# motor_endcap.net
KiCad netlist of a schematic drawn in Altium Designer
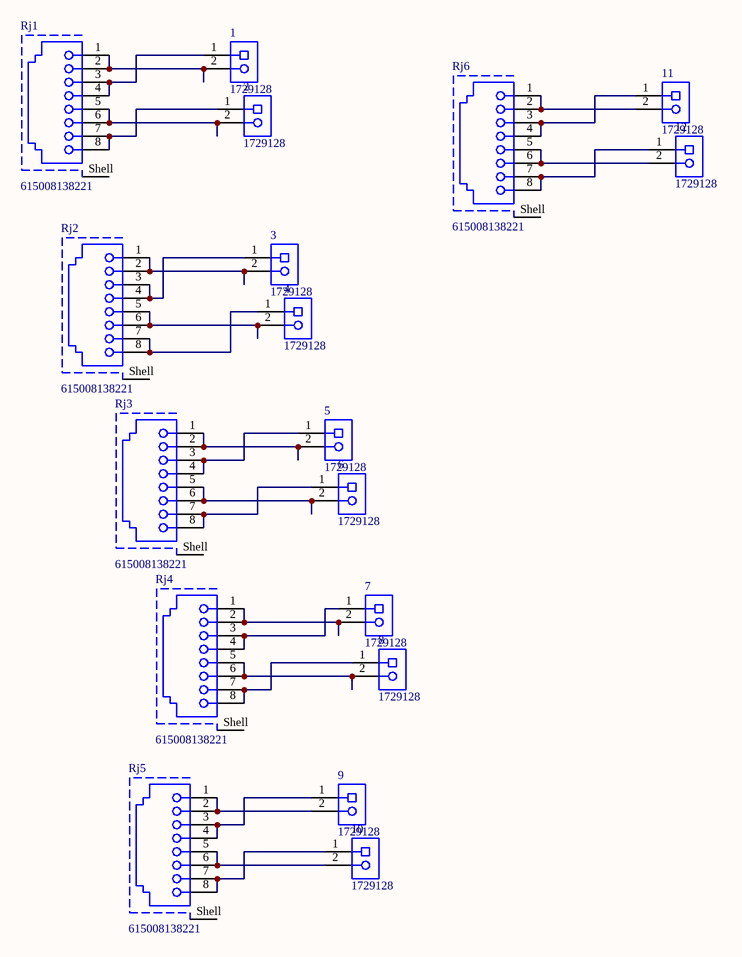
[diagram p0: motor endcap.SchDoc]

(export (version "E")
  (design (tool "Eeschema 10.0.6"))
  (components
    (comp (ref "1")
      (value "1729128")
      (footprint "PHOE-1729128-2_V")
      (description "PCB Terminal Block, 13.5 A, 400 V, 2-Pin THD, RoHS, Bulk")
      (fields (field (name "MANUFACTURER") "Phoenix Contact"))
      (libsource (lib "Altium Content Vault") (part "CN-2P-F-R2"))
    )
    (comp (ref "2")
      (value "1729128")
      (footprint "PHOE-1729128-2_V")
      (description "PCB Terminal Block, 13.5 A, 400 V, 2-Pin THD, RoHS, Bulk")
      (fields (field (name "MANUFACTURER") "Phoenix Contact"))
      (libsource (lib "Altium Content Vault") (part "CN-2P-F-R2"))
    )
    (comp (ref "3")
      (value "1729128")
      (footprint "PHOE-1729128-2_V")
      (description "PCB Terminal Block, 13.5 A, 400 V, 2-Pin THD, RoHS, Bulk")
      (fields (field (name "MANUFACTURER") "Phoenix Contact"))
      (libsource (lib "Altium Content Vault") (part "CN-2P-F-R2"))
    )
    (comp (ref "4")
      (value "1729128")
      (footprint "PHOE-1729128-2_V")
      (description "PCB Terminal Block, 13.5 A, 400 V, 2-Pin THD, RoHS, Bulk")
      (fields (field (name "MANUFACTURER") "Phoenix Contact"))
      (libsource (lib "Altium Content Vault") (part "CN-2P-F-R2"))
    )
    (comp (ref "5")
      (value "1729128")
      (footprint "PHOE-1729128-2_V")
      (description "PCB Terminal Block, 13.5 A, 400 V, 2-Pin THD, RoHS, Bulk")
      (fields (field (name "MANUFACTURER") "Phoenix Contact"))
      (libsource (lib "Altium Content Vault") (part "CN-2P-F-R2"))
    )
    (comp (ref "6")
      (value "1729128")
      (footprint "PHOE-1729128-2_V")
      (description "PCB Terminal Block, 13.5 A, 400 V, 2-Pin THD, RoHS, Bulk")
      (fields (field (name "MANUFACTURER") "Phoenix Contact"))
      (libsource (lib "Altium Content Vault") (part "CN-2P-F-R2"))
    )
    (comp (ref "7")
      (value "1729128")
      (footprint "PHOE-1729128-2_V")
      (description "PCB Terminal Block, 13.5 A, 400 V, 2-Pin THD, RoHS, Bulk")
      (fields (field (name "MANUFACTURER") "Phoenix Contact"))
      (libsource (lib "Altium Content Vault") (part "CN-2P-F-R2"))
    )
    (comp (ref "8")
      (value "1729128")
      (footprint "PHOE-1729128-2_V")
      (description "PCB Terminal Block, 13.5 A, 400 V, 2-Pin THD, RoHS, Bulk")
      (fields (field (name "MANUFACTURER") "Phoenix Contact"))
      (libsource (lib "Altium Content Vault") (part "CN-2P-F-R2"))
    )
    (comp (ref "9")
      (value "1729128")
      (footprint "PHOE-1729128-2_V")
      (description "PCB Terminal Block, 13.5 A, 400 V, 2-Pin THD, RoHS, Bulk")
      (fields (field (name "MANUFACTURER") "Phoenix Contact"))
      (libsource (lib "Altium Content Vault") (part "CN-2P-F-R2"))
    )
    (comp (ref "10")
      (value "1729128")
      (footprint "PHOE-1729128-2_V")
      (description "PCB Terminal Block, 13.5 A, 400 V, 2-Pin THD, RoHS, Bulk")
      (fields (field (name "MANUFACTURER") "Phoenix Contact"))
      (libsource (lib "Altium Content Vault") (part "CN-2P-F-R2"))
    )
    (comp (ref "11")
      (value "1729128")
      (footprint "PHOE-1729128-2_V")
      (description "PCB Terminal Block, 13.5 A, 400 V, 2-Pin THD, RoHS, Bulk")
      (fields (field (name "MANUFACTURER") "Phoenix Contact"))
      (libsource (lib "Altium Content Vault") (part "CN-2P-F-R2"))
    )
    (comp (ref "12")
      (value "1729128")
      (footprint "PHOE-1729128-2_V")
      (description "PCB Terminal Block, 13.5 A, 400 V, 2-Pin THD, RoHS, Bulk")
      (fields (field (name "MANUFACTURER") "Phoenix Contact"))
      (libsource (lib "Altium Content Vault") (part "CN-2P-F-R2"))
    )
    (comp (ref "Rj1")
      (value "615008138221")
      (footprint "615008138221")
      (libsource (lib "Altium Content Vault") (part "8P8C - 1 Port - Shielded"))
    )
    (comp (ref "Rj2")
      (value "615008138221")
      (footprint "615008138221")
      (libsource (lib "Altium Content Vault") (part "8P8C - 1 Port - Shielded"))
    )
    (comp (ref "Rj3")
      (value "615008138221")
      (footprint "615008138221")
      (libsource (lib "Altium Content Vault") (part "8P8C - 1 Port - Shielded"))
    )
    (comp (ref "Rj4")
      (value "615008138221")
      (footprint "615008138221")
      (libsource (lib "Altium Content Vault") (part "8P8C - 1 Port - Shielded"))
    )
    (comp (ref "Rj5")
      (value "615008138221")
      (footprint "615008138221")
      (libsource (lib "Altium Content Vault") (part "8P8C - 1 Port - Shielded"))
    )
    (comp (ref "Rj6")
      (value "615008138221")
      (footprint "615008138221")
      (libsource (lib "Altium Content Vault") (part "8P8C - 1 Port - Shielded"))
    )
  )
  (nets
    (net (code "1") (name "Net-(1-Pad1)") (class "Default")
      (node (ref "1") (pin "1") (pinfunction "1_1") (pintype "passive"))
      (node (ref "Rj1") (pin "3") (pinfunction "3_3") (pintype "passive"))
      (node (ref "Rj1") (pin "4") (pinfunction "4_4") (pintype "passive"))
    )
    (net (code "2") (name "Net-(1-Pad2)") (class "Default")
      (node (ref "1") (pin "2") (pinfunction "2_2") (pintype "passive"))
      (node (ref "Rj1") (pin "1") (pinfunction "1_1") (pintype "passive"))
      (node (ref "Rj1") (pin "2") (pinfunction "2_2") (pintype "passive"))
    )
    (net (code "3") (name "Net-(2-Pad1)") (class "Default")
      (node (ref "2") (pin "1") (pinfunction "1_1") (pintype "passive"))
      (node (ref "Rj1") (pin "7") (pinfunction "7_7") (pintype "passive"))
      (node (ref "Rj1") (pin "8") (pinfunction "8_8") (pintype "passive"))
    )
    (net (code "4") (name "Net-(2-Pad2)") (class "Default")
      (node (ref "2") (pin "2") (pinfunction "2_2") (pintype "passive"))
      (node (ref "Rj1") (pin "5") (pinfunction "5_5") (pintype "passive"))
      (node (ref "Rj1") (pin "6") (pinfunction "6_6") (pintype "passive"))
    )
    (net (code "5") (name "Net-(3-Pad1)") (class "Default")
      (node (ref "3") (pin "1") (pinfunction "1_1") (pintype "passive"))
      (node (ref "Rj2") (pin "3") (pinfunction "3_3") (pintype "passive"))
      (node (ref "Rj2") (pin "4") (pinfunction "4_4") (pintype "passive"))
    )
    (net (code "6") (name "Net-(3-Pad2)") (class "Default")
      (node (ref "3") (pin "2") (pinfunction "2_2") (pintype "passive"))
      (node (ref "Rj2") (pin "1") (pinfunction "1_1") (pintype "passive"))
      (node (ref "Rj2") (pin "2") (pinfunction "2_2") (pintype "passive"))
    )
    (net (code "7") (name "Net-(4-Pad1)") (class "Default")
      (node (ref "4") (pin "1") (pinfunction "1_1") (pintype "passive"))
      (node (ref "Rj2") (pin "7") (pinfunction "7_7") (pintype "passive"))
      (node (ref "Rj2") (pin "8") (pinfunction "8_8") (pintype "passive"))
    )
    (net (code "8") (name "Net-(4-Pad2)") (class "Default")
      (node (ref "4") (pin "2") (pinfunction "2_2") (pintype "passive"))
      (node (ref "Rj2") (pin "5") (pinfunction "5_5") (pintype "passive"))
      (node (ref "Rj2") (pin "6") (pinfunction "6_6") (pintype "passive"))
    )
    (net (code "9") (name "Net-(5-Pad1)") (class "Default")
      (node (ref "5") (pin "1") (pinfunction "1_1") (pintype "passive"))
      (node (ref "Rj3") (pin "3") (pinfunction "3_3") (pintype "passive"))
      (node (ref "Rj3") (pin "4") (pinfunction "4_4") (pintype "passive"))
    )
    (net (code "10") (name "Net-(5-Pad2)") (class "Default")
      (node (ref "5") (pin "2") (pinfunction "2_2") (pintype "passive"))
      (node (ref "Rj3") (pin "1") (pinfunction "1_1") (pintype "passive"))
      (node (ref "Rj3") (pin "2") (pinfunction "2_2") (pintype "passive"))
    )
    (net (code "11") (name "Net-(6-Pad1)") (class "Default")
      (node (ref "6") (pin "1") (pinfunction "1_1") (pintype "passive"))
      (node (ref "Rj3") (pin "7") (pinfunction "7_7") (pintype "passive"))
      (node (ref "Rj3") (pin "8") (pinfunction "8_8") (pintype "passive"))
    )
    (net (code "12") (name "Net-(6-Pad2)") (class "Default")
      (node (ref "6") (pin "2") (pinfunction "2_2") (pintype "passive"))
      (node (ref "Rj3") (pin "5") (pinfunction "5_5") (pintype "passive"))
      (node (ref "Rj3") (pin "6") (pinfunction "6_6") (pintype "passive"))
    )
    (net (code "13") (name "Net-(7-Pad1)") (class "Default")
      (node (ref "7") (pin "1") (pinfunction "1_1") (pintype "passive"))
      (node (ref "Rj4") (pin "3") (pinfunction "3_3") (pintype "passive"))
      (node (ref "Rj4") (pin "4") (pinfunction "4_4") (pintype "passive"))
    )
    (net (code "14") (name "Net-(7-Pad2)") (class "Default")
      (node (ref "7") (pin "2") (pinfunction "2_2") (pintype "passive"))
      (node (ref "Rj4") (pin "1") (pinfunction "1_1") (pintype "passive"))
      (node (ref "Rj4") (pin "2") (pinfunction "2_2") (pintype "passive"))
    )
    (net (code "15") (name "Net-(8-Pad1)") (class "Default")
      (node (ref "8") (pin "1") (pinfunction "1_1") (pintype "passive"))
      (node (ref "Rj4") (pin "7") (pinfunction "7_7") (pintype "passive"))
      (node (ref "Rj4") (pin "8") (pinfunction "8_8") (pintype "passive"))
    )
    (net (code "16") (name "Net-(8-Pad2)") (class "Default")
      (node (ref "8") (pin "2") (pinfunction "2_2") (pintype "passive"))
      (node (ref "Rj4") (pin "5") (pinfunction "5_5") (pintype "passive"))
      (node (ref "Rj4") (pin "6") (pinfunction "6_6") (pintype "passive"))
    )
    (net (code "17") (name "Net-(9-Pad1)") (class "Default")
      (node (ref "9") (pin "1") (pinfunction "1_1") (pintype "passive"))
      (node (ref "Rj5") (pin "3") (pinfunction "3_3") (pintype "passive"))
      (node (ref "Rj5") (pin "4") (pinfunction "4_4") (pintype "passive"))
    )
    (net (code "18") (name "Net-(9-Pad2)") (class "Default")
      (node (ref "9") (pin "2") (pinfunction "2_2") (pintype "passive"))
      (node (ref "Rj5") (pin "1") (pinfunction "1_1") (pintype "passive"))
      (node (ref "Rj5") (pin "2") (pinfunction "2_2") (pintype "passive"))
    )
    (net (code "19") (name "Net-(10-Pad1)") (class "Default")
      (node (ref "10") (pin "1") (pinfunction "1_1") (pintype "passive"))
      (node (ref "Rj5") (pin "7") (pinfunction "7_7") (pintype "passive"))
      (node (ref "Rj5") (pin "8") (pinfunction "8_8") (pintype "passive"))
    )
    (net (code "20") (name "Net-(10-Pad2)") (class "Default")
      (node (ref "10") (pin "2") (pinfunction "2_2") (pintype "passive"))
      (node (ref "Rj5") (pin "5") (pinfunction "5_5") (pintype "passive"))
      (node (ref "Rj5") (pin "6") (pinfunction "6_6") (pintype "passive"))
    )
    (net (code "21") (name "Net-(11-Pad1)") (class "Default")
      (node (ref "11") (pin "1") (pinfunction "1_1") (pintype "passive"))
      (node (ref "Rj6") (pin "3") (pinfunction "3_3") (pintype "passive"))
      (node (ref "Rj6") (pin "4") (pinfunction "4_4") (pintype "passive"))
    )
    (net (code "22") (name "Net-(11-Pad2)") (class "Default")
      (node (ref "11") (pin "2") (pinfunction "2_2") (pintype "passive"))
      (node (ref "Rj6") (pin "1") (pinfunction "1_1") (pintype "passive"))
      (node (ref "Rj6") (pin "2") (pinfunction "2_2") (pintype "passive"))
    )
    (net (code "23") (name "Net-(12-Pad1)") (class "Default")
      (node (ref "12") (pin "1") (pinfunction "1_1") (pintype "passive"))
      (node (ref "Rj6") (pin "7") (pinfunction "7_7") (pintype "passive"))
      (node (ref "Rj6") (pin "8") (pinfunction "8_8") (pintype "passive"))
    )
    (net (code "24") (name "Net-(12-Pad2)") (class "Default")
      (node (ref "12") (pin "2") (pinfunction "2_2") (pintype "passive"))
      (node (ref "Rj6") (pin "5") (pinfunction "5_5") (pintype "passive"))
      (node (ref "Rj6") (pin "6") (pinfunction "6_6") (pintype "passive"))
    )
    (net (code "25") (name "unconnected-(Rj1-PadShell)") (class "Default")
      (node (ref "Rj1") (pin "Shell") (pinfunction "Shell_Shell") (pintype "passive"))
    )
    (net (code "26") (name "unconnected-(Rj2-PadShell)") (class "Default")
      (node (ref "Rj2") (pin "Shell") (pinfunction "Shell_Shell") (pintype "passive"))
    )
    (net (code "27") (name "unconnected-(Rj3-PadShell)") (class "Default")
      (node (ref "Rj3") (pin "Shell") (pinfunction "Shell_Shell") (pintype "passive"))
    )
    (net (code "28") (name "unconnected-(Rj4-PadShell)") (class "Default")
      (node (ref "Rj4") (pin "Shell") (pinfunction "Shell_Shell") (pintype "passive"))
    )
    (net (code "29") (name "unconnected-(Rj5-PadShell)") (class "Default")
      (node (ref "Rj5") (pin "Shell") (pinfunction "Shell_Shell") (pintype "passive"))
    )
    (net (code "30") (name "unconnected-(Rj6-PadShell)") (class "Default")
      (node (ref "Rj6") (pin "Shell") (pinfunction "Shell_Shell") (pintype "passive"))
    )
  )
)
